# PWR_Buck_2V_4V_4A.net
KiCad netlist of a schematic drawn in Altium Designer
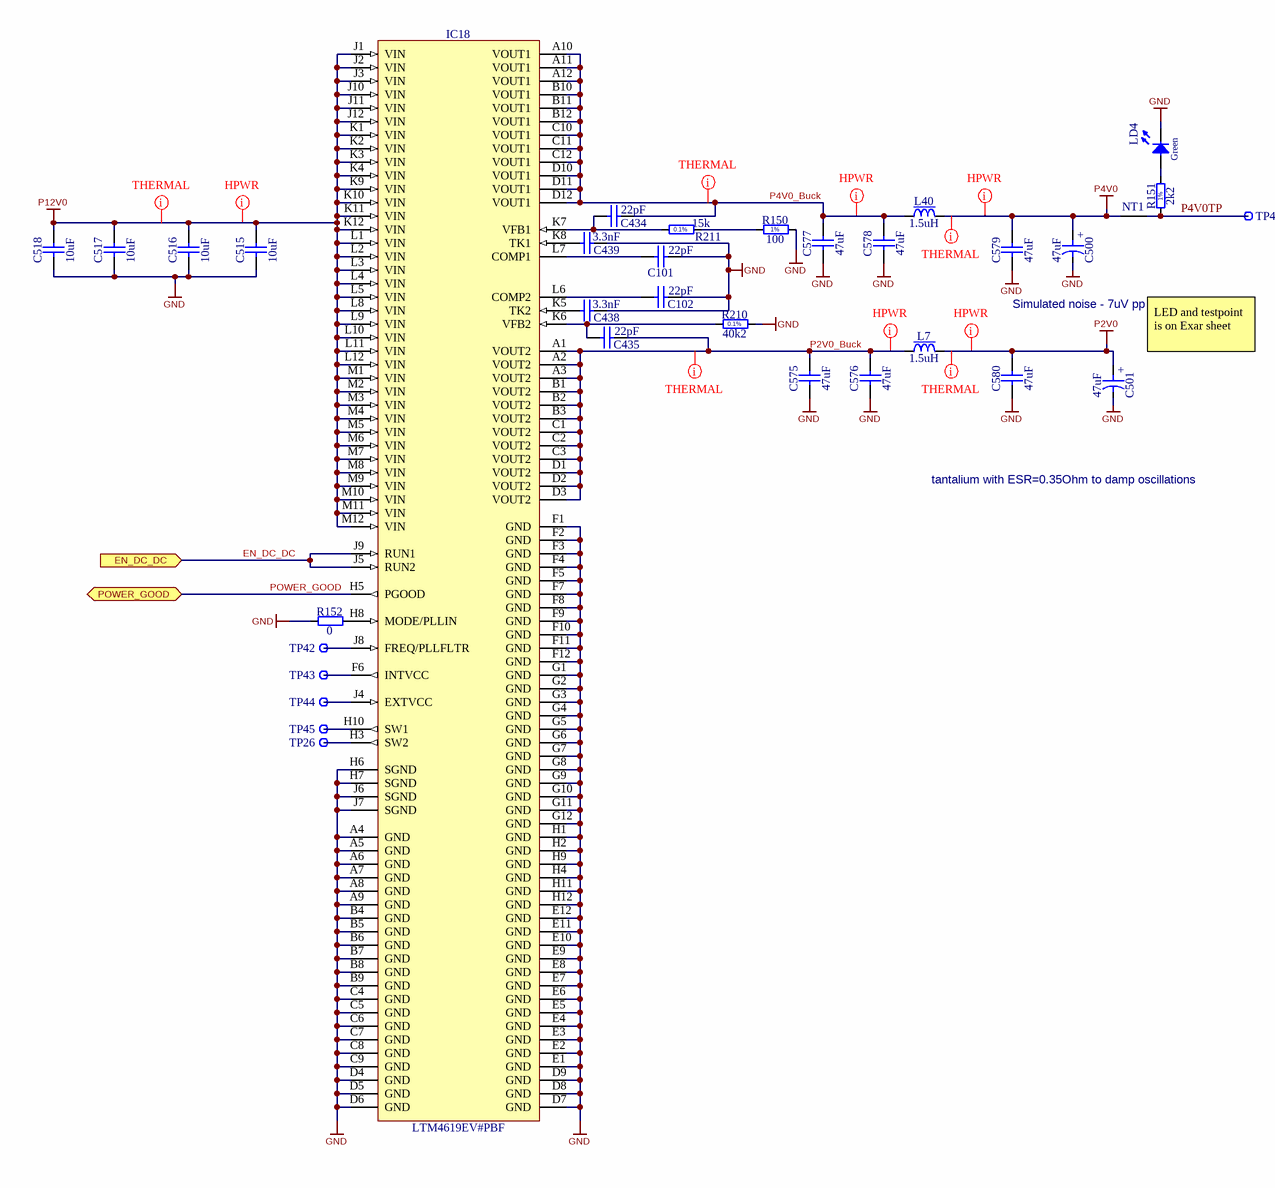
[diagram p0: PWR_Buck_2V_4V_4A.SchDoc]

(export (version "E")
  (design (tool "Eeschema 10.0.6"))
  (components
    (comp (ref "C101")
      (value "22pF")
      (footprint "CAPC1005X55N")
      (description "Non-polarised capacitor")
      (fields
        (field (name "MANUFACTURER PART NUMBER") "CC0402_22PF_50V_5%_C0G")
        (field (name "MANUFACTURER") "GENERIC")
        (field (name "AUTHOR") "CERN DEM JLC")
      )
      (libsource (lib "Capacitors") (part "Capacitor - non polarized"))
    )
    (comp (ref "C102")
      (value "22pF")
      (footprint "CAPC1005X55N")
      (description "Non-polarised capacitor")
      (fields
        (field (name "MANUFACTURER PART NUMBER") "CC0402_22PF_50V_5%_C0G")
        (field (name "MANUFACTURER") "GENERIC")
        (field (name "AUTHOR") "CERN DEM JLC")
      )
      (libsource (lib "Capacitors") (part "Capacitor - non polarized"))
    )
    (comp (ref "C434")
      (value "22pF")
      (footprint "CAPC1005X55N")
      (description "Non-polarised capacitor")
      (fields
        (field (name "MANUFACTURER PART NUMBER") "CC0402_22PF_50V_5%_C0G")
        (field (name "MANUFACTURER") "GENERIC")
        (field (name "AUTHOR") "CERN DEM JLC")
      )
      (libsource (lib "Capacitors") (part "Capacitor - non polarized"))
    )
    (comp (ref "C435")
      (value "22pF")
      (footprint "CAPC1005X55N")
      (description "Non-polarised capacitor")
      (fields
        (field (name "MANUFACTURER PART NUMBER") "CC0402_22PF_50V_5%_C0G")
        (field (name "MANUFACTURER") "GENERIC")
        (field (name "AUTHOR") "CERN DEM JLC")
      )
      (libsource (lib "Capacitors") (part "Capacitor - non polarized"))
    )
    (comp (ref "C438")
      (value "3.3nF")
      (footprint "CAPC1005X55N")
      (description "Non-polarised capacitor")
      (fields
        (field (name "MANUFACTURER PART NUMBER") "CC0402_3.3NF_50V_10%_X7R")
        (field (name "MANUFACTURER") "GENERIC")
        (field (name "AUTHOR") "CERN DEM JLC")
      )
      (libsource (lib "Capacitors") (part "Capacitor - non polarized"))
    )
    (comp (ref "C439")
      (value "3.3nF")
      (footprint "CAPC1005X55N")
      (description "Non-polarised capacitor")
      (fields
        (field (name "MANUFACTURER PART NUMBER") "CC0402_3.3NF_50V_10%_X7R")
        (field (name "MANUFACTURER") "GENERIC")
        (field (name "AUTHOR") "CERN DEM JLC")
      )
      (libsource (lib "Capacitors") (part "Capacitor - non polarized"))
    )
    (comp (ref "C500")
      (value "47uF")
      (footprint "CAPMP6032X280N")
      (description "Polarised capacitor")
      (fields
        (field (name "MANUFACTURER PART NUMBER") "CTE6032-28_47UF_16V_10%_LESR0350")
        (field (name "MANUFACTURER") "GENERIC")
        (field (name "AUTHOR") "CERN DEM JLC")
      )
      (libsource (lib "Capacitors") (part "Capacitor - polarized"))
    )
    (comp (ref "C501")
      (value "47uF")
      (footprint "CAPMP6032X280N")
      (description "Polarised capacitor")
      (fields
        (field (name "MANUFACTURER PART NUMBER") "CTE6032-28_47UF_16V_10%_LESR0350")
        (field (name "MANUFACTURER") "GENERIC")
        (field (name "AUTHOR") "CERN DEM JLC")
      )
      (libsource (lib "Capacitors") (part "Capacitor - polarized"))
    )
    (comp (ref "C515")
      (value "10uF")
      (footprint "CAPC2012X95N")
      (description "Non-polarised capacitor")
      (fields
        (field (name "MANUFACTURER PART NUMBER") "CC0805_10UF_25V_10%_X5R")
        (field (name "MANUFACTURER") "GENERIC")
        (field (name "AUTHOR") "CERN DEM JLC")
      )
      (libsource (lib "Capacitors") (part "Capacitor - non polarized"))
    )
    (comp (ref "C516")
      (value "10uF")
      (footprint "CAPC2012X95N")
      (description "Non-polarised capacitor")
      (fields
        (field (name "MANUFACTURER PART NUMBER") "CC0805_10UF_25V_10%_X5R")
        (field (name "MANUFACTURER") "GENERIC")
        (field (name "AUTHOR") "CERN DEM JLC")
      )
      (libsource (lib "Capacitors") (part "Capacitor - non polarized"))
    )
    (comp (ref "C517")
      (value "10uF")
      (footprint "CAPC2012X95N")
      (description "Non-polarised capacitor")
      (fields
        (field (name "MANUFACTURER PART NUMBER") "CC0805_10UF_25V_10%_X5R")
        (field (name "MANUFACTURER") "GENERIC")
        (field (name "AUTHOR") "CERN DEM JLC")
      )
      (libsource (lib "Capacitors") (part "Capacitor - non polarized"))
    )
    (comp (ref "C518")
      (value "10uF")
      (footprint "CAPC2012X95N")
      (description "Non-polarised capacitor")
      (fields
        (field (name "MANUFACTURER PART NUMBER") "CC0805_10UF_25V_10%_X5R")
        (field (name "MANUFACTURER") "GENERIC")
        (field (name "AUTHOR") "CERN DEM JLC")
      )
      (libsource (lib "Capacitors") (part "Capacitor - non polarized"))
    )
    (comp (ref "C575")
      (value "47uF")
      (footprint "CAPC3225X270N")
      (description "Non-polarised capacitor")
      (fields
        (field (name "MANUFACTURER PART NUMBER") "CC1210_47UF_10V_10%_X7R")
        (field (name "MANUFACTURER") "GENERIC")
        (field (name "AUTHOR") "CERN DEM BC")
      )
      (libsource (lib "Capacitors") (part "Capacitor - non polarized"))
    )
    (comp (ref "C576")
      (value "47uF")
      (footprint "CAPC3225X270N")
      (description "Non-polarised capacitor")
      (fields
        (field (name "MANUFACTURER PART NUMBER") "CC1210_47UF_10V_10%_X7R")
        (field (name "MANUFACTURER") "GENERIC")
        (field (name "AUTHOR") "CERN DEM BC")
      )
      (libsource (lib "Capacitors") (part "Capacitor - non polarized"))
    )
    (comp (ref "C577")
      (value "47uF")
      (footprint "CAPC3225X270N")
      (description "Non-polarised capacitor")
      (fields
        (field (name "MANUFACTURER PART NUMBER") "CC1210_47UF_10V_10%_X7R")
        (field (name "MANUFACTURER") "GENERIC")
        (field (name "AUTHOR") "CERN DEM BC")
      )
      (libsource (lib "Capacitors") (part "Capacitor - non polarized"))
    )
    (comp (ref "C578")
      (value "47uF")
      (footprint "CAPC3225X270N")
      (description "Non-polarised capacitor")
      (fields
        (field (name "MANUFACTURER PART NUMBER") "CC1210_47UF_10V_10%_X7R")
        (field (name "MANUFACTURER") "GENERIC")
        (field (name "AUTHOR") "CERN DEM BC")
      )
      (libsource (lib "Capacitors") (part "Capacitor - non polarized"))
    )
    (comp (ref "C579")
      (value "47uF")
      (footprint "CAPC3225X270N")
      (description "Non-polarised capacitor")
      (fields
        (field (name "MANUFACTURER PART NUMBER") "CC1210_47UF_10V_10%_X7R")
        (field (name "MANUFACTURER") "GENERIC")
        (field (name "AUTHOR") "CERN DEM BC")
      )
      (libsource (lib "Capacitors") (part "Capacitor - non polarized"))
    )
    (comp (ref "C580")
      (value "47uF")
      (footprint "CAPC3225X270N")
      (description "Non-polarised capacitor")
      (fields
        (field (name "MANUFACTURER PART NUMBER") "CC1210_47UF_10V_10%_X7R")
        (field (name "MANUFACTURER") "GENERIC")
        (field (name "AUTHOR") "CERN DEM BC")
      )
      (libsource (lib "Capacitors") (part "Capacitor - non polarized"))
    )
    (comp (ref "IC18")
      (value "LTM4619EV#PBF")
      (footprint "LGA144S127P12X12_1500X1500X292R")
      (description "4.5V-26.5V To 0.8V-5V, Iout 4A Dual DC/DC uModule Regulator")
      (fields (field (name "MANUFACTURER") "LINEAR TECHNOLOGY") (field (name "AUTHOR") "CERN DEM JLC"))
      (libsource (lib "ICs And Semiconductors") (part "LTM4619"))
    )
    (comp (ref "L7")
      (value "1.5uH")
      (footprint "IND_TDK_SPM6530")
      (description "Inductor With Core")
      (fields
        (field (name "MANUFACTURER PART NUMBER") "SPM6530T-1R5M100")
        (field (name "MANUFACTURER") "TDK")
        (field (name "AUTHOR") "CERN DEM MR")
      )
      (libsource (lib "Inductors & Transformers") (part "Inductor With Magnetic core"))
    )
    (comp (ref "L40")
      (value "1.5uH")
      (footprint "IND_TDK_SPM6530")
      (description "Inductor With Core")
      (fields
        (field (name "MANUFACTURER PART NUMBER") "SPM6530T-1R5M100")
        (field (name "MANUFACTURER") "TDK")
        (field (name "AUTHOR") "CERN DEM MR")
      )
      (libsource (lib "Inductors & Transformers") (part "Inductor With Magnetic core"))
    )
    (comp (ref "LD4")
      (value "Green")
      (footprint "LED_KINGBRIGHT_KPH-1608CGCK")
      (description "LED Green 1C 2A")
      (fields
        (field (name "MANUFACTURER PART NUMBER") "KPH-1608CGCK")
        (field (name "MANUFACTURER") "KINGBRIGHT")
        (field (name "AUTHOR") "CERN DEM JLC")
      )
      (libsource (lib "ICs And Semiconductors") (part "LED Green 1C 2A"))
    )
    (comp (ref "NT1")
      (value "Net Tie")
      (footprint "Net Tie")
      (fields (field (name "AUTHOR") "CERN DEM JLC"))
      (libsource (lib "Eletro-mechanical") (part "Net Tie"))
    )
    (comp (ref "R150")
      (value "100")
      (footprint "RESC1005X40N")
      (description "Resistor - 1%")
      (fields
        (field (name "MANUFACTURER PART NUMBER") "R0402_100R_1%_0.0625W_100PPM")
        (field (name "MANUFACTURER") "GENERIC")
        (field (name "AUTHOR") "CERN DEM JLC")
      )
      (libsource (lib "Resistors") (part "Resistor - 1%"))
    )
    (comp (ref "R151")
      (value "2k2")
      (footprint "RESC1005X40N")
      (description "Resistor - 1%")
      (fields
        (field (name "MANUFACTURER PART NUMBER") "R0402_2K2_1%_0.0625W_100PPM")
        (field (name "MANUFACTURER") "GENERIC")
        (field (name "AUTHOR") "CERN DEM JLC")
      )
      (libsource (lib "Resistors") (part "Resistor - 1%"))
    )
    (comp (ref "R152")
      (value "0")
      (footprint "RESC1005X40N")
      (description "Resistor")
      (fields
        (field (name "MANUFACTURER PART NUMBER") "R0402_0R_JUMPER")
        (field (name "MANUFACTURER") "GENERIC")
        (field (name "AUTHOR") "CERN DEM JLC")
      )
      (libsource (lib "Resistors") (part "Resistor"))
    )
    (comp (ref "R210")
      (value "40k2")
      (footprint "RESC1608X55N")
      (description "Resistor - 0.1%")
      (fields
        (field (name "MANUFACTURER PART NUMBER") "R0603_40K2_0.1%_0.063W_10PPM")
        (field (name "MANUFACTURER") "GENERIC")
        (field (name "AUTHOR") "CERN DEM JLC")
      )
      (libsource (lib "Resistors") (part "Resistor - 0.1%"))
    )
    (comp (ref "R211")
      (value "15k")
      (footprint "RESC1608X55N")
      (description "Resistor - 0.1%")
      (fields
        (field (name "MANUFACTURER PART NUMBER") "R0603_15K_0.1%_0.063W_10PPM")
        (field (name "MANUFACTURER") "GENERIC")
        (field (name "AUTHOR") "CERN DEM JLC")
      )
      (libsource (lib "Resistors") (part "Resistor - 0.1%"))
    )
    (comp (ref "TP26")
      (value "Test Point")
      (footprint "TPS127")
      (fields (field (name "PART NUMBER") "SMD_PAD_1.27X1.27MM") (field (name "AUTHOR") "CERN DEM JLC"))
      (libsource (lib "Eletro-mechanical") (part "Test Point"))
    )
    (comp (ref "TP41")
      (value "Test Point")
      (footprint "TPS127")
      (fields (field (name "PART NUMBER") "SMD_PAD_1.27X1.27MM") (field (name "AUTHOR") "CERN DEM JLC"))
      (libsource (lib "Eletro-mechanical") (part "Test Point"))
    )
    (comp (ref "TP42")
      (value "Test Point")
      (footprint "TPS127")
      (fields (field (name "PART NUMBER") "SMD_PAD_1.27X1.27MM") (field (name "AUTHOR") "CERN DEM JLC"))
      (libsource (lib "Eletro-mechanical") (part "Test Point"))
    )
    (comp (ref "TP43")
      (value "Test Point")
      (footprint "TPS127")
      (fields (field (name "PART NUMBER") "SMD_PAD_1.27X1.27MM") (field (name "AUTHOR") "CERN DEM JLC"))
      (libsource (lib "Eletro-mechanical") (part "Test Point"))
    )
    (comp (ref "TP44")
      (value "Test Point")
      (footprint "TPS127")
      (fields (field (name "PART NUMBER") "SMD_PAD_1.27X1.27MM") (field (name "AUTHOR") "CERN DEM JLC"))
      (libsource (lib "Eletro-mechanical") (part "Test Point"))
    )
    (comp (ref "TP45")
      (value "Test Point")
      (footprint "TPS127")
      (fields (field (name "PART NUMBER") "SMD_PAD_1.27X1.27MM") (field (name "AUTHOR") "CERN DEM JLC"))
      (libsource (lib "Eletro-mechanical") (part "Test Point"))
    )
  )
  (nets
    (net (code "1") (name "/EN_DC_DC") (class "Default")
      (node (ref "IC18") (pin "J5") (pinfunction "RUN2_J5") (pintype "input"))
      (node (ref "IC18") (pin "J9") (pinfunction "RUN1_J9") (pintype "input"))
    )
    (net (code "2") (name "/P2V0_Buck") (class "Default")
      (node (ref "C435") (pin "1") (pinfunction "1_1") (pintype "passive"))
      (node (ref "C575") (pin "2") (pinfunction "2_2") (pintype "passive"))
      (node (ref "C576") (pin "2") (pinfunction "2_2") (pintype "passive"))
      (node (ref "IC18") (pin "A1") (pinfunction "VOUT2_A1") (pintype "power_in"))
      (node (ref "IC18") (pin "A2") (pinfunction "VOUT2_A2") (pintype "power_in"))
      (node (ref "IC18") (pin "A3") (pinfunction "VOUT2_A3") (pintype "power_in"))
      (node (ref "IC18") (pin "B1") (pinfunction "VOUT2_B1") (pintype "power_in"))
      (node (ref "IC18") (pin "B2") (pinfunction "VOUT2_B2") (pintype "power_in"))
      (node (ref "IC18") (pin "B3") (pinfunction "VOUT2_B3") (pintype "power_in"))
      (node (ref "IC18") (pin "C1") (pinfunction "VOUT2_C1") (pintype "power_in"))
      (node (ref "IC18") (pin "C2") (pinfunction "VOUT2_C2") (pintype "power_in"))
      (node (ref "IC18") (pin "C3") (pinfunction "VOUT2_C3") (pintype "power_in"))
      (node (ref "IC18") (pin "D1") (pinfunction "VOUT2_D1") (pintype "power_in"))
      (node (ref "IC18") (pin "D2") (pinfunction "VOUT2_D2") (pintype "power_in"))
      (node (ref "IC18") (pin "D3") (pinfunction "VOUT2_D3") (pintype "power_in"))
      (node (ref "L7") (pin "1") (pinfunction "1_1") (pintype "passive"))
    )
    (net (code "3") (name "/P4V0TP") (class "Default")
      (node (ref "NT1") (pin "2") (pinfunction "2_2") (pintype "bidirectional"))
      (node (ref "R151") (pin "1") (pinfunction "1_1") (pintype "passive"))
      (node (ref "TP41") (pin "1") (pinfunction "1_1") (pintype "bidirectional"))
    )
    (net (code "4") (name "/P4V0_Buck") (class "Default")
      (node (ref "C434") (pin "1") (pinfunction "1_1") (pintype "passive"))
      (node (ref "C577") (pin "2") (pinfunction "2_2") (pintype "passive"))
      (node (ref "C578") (pin "2") (pinfunction "2_2") (pintype "passive"))
      (node (ref "IC18") (pin "A10") (pinfunction "VOUT1_A10") (pintype "power_in"))
      (node (ref "IC18") (pin "A11") (pinfunction "VOUT1_A11") (pintype "power_in"))
      (node (ref "IC18") (pin "A12") (pinfunction "VOUT1_A12") (pintype "power_in"))
      (node (ref "IC18") (pin "B10") (pinfunction "VOUT1_B10") (pintype "power_in"))
      (node (ref "IC18") (pin "B11") (pinfunction "VOUT1_B11") (pintype "power_in"))
      (node (ref "IC18") (pin "B12") (pinfunction "VOUT1_B12") (pintype "power_in"))
      (node (ref "IC18") (pin "C10") (pinfunction "VOUT1_C10") (pintype "power_in"))
      (node (ref "IC18") (pin "C11") (pinfunction "VOUT1_C11") (pintype "power_in"))
      (node (ref "IC18") (pin "C12") (pinfunction "VOUT1_C12") (pintype "power_in"))
      (node (ref "IC18") (pin "D10") (pinfunction "VOUT1_D10") (pintype "power_in"))
      (node (ref "IC18") (pin "D11") (pinfunction "VOUT1_D11") (pintype "power_in"))
      (node (ref "IC18") (pin "D12") (pinfunction "VOUT1_D12") (pintype "power_in"))
      (node (ref "L40") (pin "1") (pinfunction "1_1") (pintype "passive"))
    )
    (net (code "5") (name "/POWER_GOOD") (class "Default")
      (node (ref "IC18") (pin "H5") (pinfunction "PGOOD_H5") (pintype "output"))
    )
    (net (code "6") (name "GND") (class "Default")
      (node (ref "C101") (pin "1") (pinfunction "1_1") (pintype "passive"))
      (node (ref "C102") (pin "1") (pinfunction "1_1") (pintype "passive"))
      (node (ref "C438") (pin "2") (pinfunction "2_2") (pintype "passive"))
      (node (ref "C439") (pin "2") (pinfunction "2_2") (pintype "passive"))
      (node (ref "C500") (pin "2") (pinfunction "2_2") (pintype "passive"))
      (node (ref "C501") (pin "2") (pinfunction "2_2") (pintype "passive"))
      (node (ref "C515") (pin "1") (pinfunction "1_1") (pintype "passive"))
      (node (ref "C516") (pin "1") (pinfunction "1_1") (pintype "passive"))
      (node (ref "C517") (pin "1") (pinfunction "1_1") (pintype "passive"))
      (node (ref "C518") (pin "1") (pinfunction "1_1") (pintype "passive"))
      (node (ref "C575") (pin "1") (pinfunction "1_1") (pintype "passive"))
      (node (ref "C576") (pin "1") (pinfunction "1_1") (pintype "passive"))
      (node (ref "C577") (pin "1") (pinfunction "1_1") (pintype "passive"))
      (node (ref "C578") (pin "1") (pinfunction "1_1") (pintype "passive"))
      (node (ref "C579") (pin "1") (pinfunction "1_1") (pintype "passive"))
      (node (ref "C580") (pin "1") (pinfunction "1_1") (pintype "passive"))
      (node (ref "IC18") (pin "A4") (pinfunction "GND_A4") (pintype "power_in"))
      (node (ref "IC18") (pin "A5") (pinfunction "GND_A5") (pintype "power_in"))
      (node (ref "IC18") (pin "A6") (pinfunction "GND_A6") (pintype "power_in"))
      (node (ref "IC18") (pin "A7") (pinfunction "GND_A7") (pintype "power_in"))
      (node (ref "IC18") (pin "A8") (pinfunction "GND_A8") (pintype "power_in"))
      (node (ref "IC18") (pin "A9") (pinfunction "GND_A9") (pintype "power_in"))
      (node (ref "IC18") (pin "B4") (pinfunction "GND_B4") (pintype "power_in"))
      (node (ref "IC18") (pin "B5") (pinfunction "GND_B5") (pintype "power_in"))
      (node (ref "IC18") (pin "B6") (pinfunction "GND_B6") (pintype "power_in"))
      (node (ref "IC18") (pin "B7") (pinfunction "GND_B7") (pintype "power_in"))
      (node (ref "IC18") (pin "B8") (pinfunction "GND_B8") (pintype "power_in"))
      (node (ref "IC18") (pin "B9") (pinfunction "GND_B9") (pintype "power_in"))
      (node (ref "IC18") (pin "C4") (pinfunction "GND_C4") (pintype "power_in"))
      (node (ref "IC18") (pin "C5") (pinfunction "GND_C5") (pintype "power_in"))
      (node (ref "IC18") (pin "C6") (pinfunction "GND_C6") (pintype "power_in"))
      (node (ref "IC18") (pin "C7") (pinfunction "GND_C7") (pintype "power_in"))
      (node (ref "IC18") (pin "C8") (pinfunction "GND_C8") (pintype "power_in"))
      (node (ref "IC18") (pin "C9") (pinfunction "GND_C9") (pintype "power_in"))
      (node (ref "IC18") (pin "D4") (pinfunction "GND_D4") (pintype "power_in"))
      (node (ref "IC18") (pin "D5") (pinfunction "GND_D5") (pintype "power_in"))
      (node (ref "IC18") (pin "D6") (pinfunction "GND_D6") (pintype "power_in"))
      (node (ref "IC18") (pin "D7") (pinfunction "GND_D7") (pintype "power_in"))
      (node (ref "IC18") (pin "D8") (pinfunction "GND_D8") (pintype "power_in"))
      (node (ref "IC18") (pin "D9") (pinfunction "GND_D9") (pintype "power_in"))
      (node (ref "IC18") (pin "E1") (pinfunction "GND_E1") (pintype "power_in"))
      (node (ref "IC18") (pin "E10") (pinfunction "GND_E10") (pintype "power_in"))
      (node (ref "IC18") (pin "E11") (pinfunction "GND_E11") (pintype "power_in"))
      (node (ref "IC18") (pin "E12") (pinfunction "GND_E12") (pintype "power_in"))
      (node (ref "IC18") (pin "E2") (pinfunction "GND_E2") (pintype "power_in"))
      (node (ref "IC18") (pin "E3") (pinfunction "GND_E3") (pintype "power_in"))
      (node (ref "IC18") (pin "E4") (pinfunction "GND_E4") (pintype "power_in"))
      (node (ref "IC18") (pin "E5") (pinfunction "GND_E5") (pintype "power_in"))
      (node (ref "IC18") (pin "E6") (pinfunction "GND_E6") (pintype "power_in"))
      (node (ref "IC18") (pin "E7") (pinfunction "GND_E7") (pintype "power_in"))
      (node (ref "IC18") (pin "E8") (pinfunction "GND_E8") (pintype "power_in"))
      (node (ref "IC18") (pin "E9") (pinfunction "GND_E9") (pintype "power_in"))
      (node (ref "IC18") (pin "F1") (pinfunction "GND_F1") (pintype "power_in"))
      (node (ref "IC18") (pin "F10") (pinfunction "GND_F10") (pintype "power_in"))
      (node (ref "IC18") (pin "F11") (pinfunction "GND_F11") (pintype "power_in"))
      (node (ref "IC18") (pin "F12") (pinfunction "GND_F12") (pintype "power_in"))
      (node (ref "IC18") (pin "F2") (pinfunction "GND_F2") (pintype "power_in"))
      (node (ref "IC18") (pin "F3") (pinfunction "GND_F3") (pintype "power_in"))
      (node (ref "IC18") (pin "F4") (pinfunction "GND_F4") (pintype "power_in"))
      (node (ref "IC18") (pin "F5") (pinfunction "GND_F5") (pintype "power_in"))
      (node (ref "IC18") (pin "F7") (pinfunction "GND_F7") (pintype "power_in"))
      (node (ref "IC18") (pin "F8") (pinfunction "GND_F8") (pintype "power_in"))
      (node (ref "IC18") (pin "F9") (pinfunction "GND_F9") (pintype "power_in"))
      (node (ref "IC18") (pin "G1") (pinfunction "GND_G1") (pintype "power_in"))
      (node (ref "IC18") (pin "G10") (pinfunction "GND_G10") (pintype "power_in"))
      (node (ref "IC18") (pin "G11") (pinfunction "GND_G11") (pintype "power_in"))
      (node (ref "IC18") (pin "G12") (pinfunction "GND_G12") (pintype "power_in"))
      (node (ref "IC18") (pin "G2") (pinfunction "GND_G2") (pintype "power_in"))
      (node (ref "IC18") (pin "G3") (pinfunction "GND_G3") (pintype "power_in"))
      (node (ref "IC18") (pin "G4") (pinfunction "GND_G4") (pintype "power_in"))
      (node (ref "IC18") (pin "G5") (pinfunction "GND_G5") (pintype "power_in"))
      (node (ref "IC18") (pin "G6") (pinfunction "GND_G6") (pintype "power_in"))
      (node (ref "IC18") (pin "G7") (pinfunction "GND_G7") (pintype "power_in"))
      (node (ref "IC18") (pin "G8") (pinfunction "GND_G8") (pintype "power_in"))
      (node (ref "IC18") (pin "G9") (pinfunction "GND_G9") (pintype "power_in"))
      (node (ref "IC18") (pin "H1") (pinfunction "GND_H1") (pintype "power_in"))
      (node (ref "IC18") (pin "H11") (pinfunction "GND_H11") (pintype "power_in"))
      (node (ref "IC18") (pin "H12") (pinfunction "GND_H12") (pintype "power_in"))
      (node (ref "IC18") (pin "H2") (pinfunction "GND_H2") (pintype "power_in"))
      (node (ref "IC18") (pin "H4") (pinfunction "GND_H4") (pintype "power_in"))
      (node (ref "IC18") (pin "H6") (pinfunction "SGND_H6") (pintype "power_in"))
      (node (ref "IC18") (pin "H7") (pinfunction "SGND_H7") (pintype "power_in"))
      (node (ref "IC18") (pin "H9") (pinfunction "GND_H9") (pintype "power_in"))
      (node (ref "IC18") (pin "J6") (pinfunction "SGND_J6") (pintype "power_in"))
      (node (ref "IC18") (pin "J7") (pinfunction "SGND_J7") (pintype "power_in"))
      (node (ref "LD4") (pin "1") (pinfunction "C_1") (pintype "passive"))
      (node (ref "R150") (pin "2") (pinfunction "2_2") (pintype "passive"))
      (node (ref "R152") (pin "1") (pinfunction "1_1") (pintype "passive"))
      (node (ref "R210") (pin "2") (pinfunction "2_2") (pintype "passive"))
    )
    (net (code "7") (name "Net-(IC18-COMP1)") (class "Default")
      (node (ref "C101") (pin "2") (pinfunction "2_2") (pintype "passive"))
      (node (ref "IC18") (pin "L7") (pinfunction "COMP1_L7") (pintype "passive"))
    )
    (net (code "8") (name "Net-(IC18-COMP2)") (class "Default")
      (node (ref "C102") (pin "2") (pinfunction "2_2") (pintype "passive"))
      (node (ref "IC18") (pin "L6") (pinfunction "COMP2_L6") (pintype "passive"))
    )
    (net (code "9") (name "Net-(IC18-EXTVCC)") (class "Default")
      (node (ref "IC18") (pin "J4") (pinfunction "EXTVCC_J4") (pintype "input"))
      (node (ref "TP44") (pin "1") (pinfunction "1_1") (pintype "bidirectional"))
    )
    (net (code "10") (name "Net-(IC18-FREQ{slash}PLLFLTR)") (class "Default")
      (node (ref "IC18") (pin "J8") (pinfunction "FREQ/PLLFLTR_J8") (pintype "input"))
      (node (ref "TP42") (pin "1") (pinfunction "1_1") (pintype "bidirectional"))
    )
    (net (code "11") (name "Net-(IC18-INTVCC)") (class "Default")
      (node (ref "IC18") (pin "F6") (pinfunction "INTVCC_F6") (pintype "output"))
      (node (ref "TP43") (pin "1") (pinfunction "1_1") (pintype "bidirectional"))
    )
    (net (code "12") (name "Net-(IC18-MODE{slash}PLLIN)") (class "Default")
      (node (ref "IC18") (pin "H8") (pinfunction "MODE/PLLIN_H8") (pintype "input"))
      (node (ref "R152") (pin "2") (pinfunction "2_2") (pintype "passive"))
    )
    (net (code "13") (name "Net-(IC18-SW1)") (class "Default")
      (node (ref "IC18") (pin "H10") (pinfunction "SW1_H10") (pintype "output"))
      (node (ref "TP45") (pin "1") (pinfunction "1_1") (pintype "bidirectional"))
    )
    (net (code "14") (name "Net-(IC18-SW2)") (class "Default")
      (node (ref "IC18") (pin "H3") (pinfunction "SW2_H3") (pintype "output"))
      (node (ref "TP26") (pin "1") (pinfunction "1_1") (pintype "bidirectional"))
    )
    (net (code "15") (name "Net-(IC18-TK1)") (class "Default")
      (node (ref "C439") (pin "1") (pinfunction "1_1") (pintype "passive"))
      (node (ref "IC18") (pin "K8") (pinfunction "TK1_K8") (pintype "input"))
    )
    (net (code "16") (name "Net-(IC18-TK2)") (class "Default")
      (node (ref "C438") (pin "1") (pinfunction "1_1") (pintype "passive"))
      (node (ref "IC18") (pin "K5") (pinfunction "TK2_K5") (pintype "input"))
    )
    (net (code "17") (name "Net-(IC18-VFB1)") (class "Default")
      (node (ref "C434") (pin "2") (pinfunction "2_2") (pintype "passive"))
      (node (ref "IC18") (pin "K7") (pinfunction "VFB1_K7") (pintype "input"))
      (node (ref "R211") (pin "1") (pinfunction "1_1") (pintype "passive"))
    )
    (net (code "18") (name "Net-(IC18-VFB2)") (class "Default")
      (node (ref "C435") (pin "2") (pinfunction "2_2") (pintype "passive"))
      (node (ref "IC18") (pin "K6") (pinfunction "VFB2_K6") (pintype "input"))
      (node (ref "R210") (pin "1") (pinfunction "1_1") (pintype "passive"))
    )
    (net (code "19") (name "Net-(LD4-A)") (class "Default")
      (node (ref "LD4") (pin "2") (pinfunction "A_2") (pintype "passive"))
      (node (ref "R151") (pin "2") (pinfunction "2_2") (pintype "passive"))
    )
    (net (code "20") (name "Net-(R150-Pad1)") (class "Default")
      (node (ref "R150") (pin "1") (pinfunction "1_1") (pintype "passive"))
      (node (ref "R211") (pin "2") (pinfunction "2_2") (pintype "passive"))
    )
    (net (code "21") (name "P2V0") (class "Default")
      (node (ref "C501") (pin "1") (pinfunction "1_1") (pintype "passive"))
      (node (ref "C580") (pin "2") (pinfunction "2_2") (pintype "passive"))
      (node (ref "L7") (pin "2") (pinfunction "2_2") (pintype "passive"))
    )
    (net (code "22") (name "P4V0") (class "Default")
      (node (ref "C500") (pin "1") (pinfunction "1_1") (pintype "passive"))
      (node (ref "C579") (pin "2") (pinfunction "2_2") (pintype "passive"))
      (node (ref "L40") (pin "2") (pinfunction "2_2") (pintype "passive"))
      (node (ref "NT1") (pin "1") (pinfunction "1_1") (pintype "bidirectional"))
    )
    (net (code "23") (name "P12V0") (class "Default")
      (node (ref "C515") (pin "2") (pinfunction "2_2") (pintype "passive"))
      (node (ref "C516") (pin "2") (pinfunction "2_2") (pintype "passive"))
      (node (ref "C517") (pin "2") (pinfunction "2_2") (pintype "passive"))
      (node (ref "C518") (pin "2") (pinfunction "2_2") (pintype "passive"))
      (node (ref "IC18") (pin "J1") (pinfunction "VIN_J1") (pintype "input"))
      (node (ref "IC18") (pin "J10") (pinfunction "VIN_J10") (pintype "input"))
      (node (ref "IC18") (pin "J11") (pinfunction "VIN_J11") (pintype "input"))
      (node (ref "IC18") (pin "J12") (pinfunction "VIN_J12") (pintype "input"))
      (node (ref "IC18") (pin "J2") (pinfunction "VIN_J2") (pintype "input"))
      (node (ref "IC18") (pin "J3") (pinfunction "VIN_J3") (pintype "input"))
      (node (ref "IC18") (pin "K1") (pinfunction "VIN_K1") (pintype "input"))
      (node (ref "IC18") (pin "K10") (pinfunction "VIN_K10") (pintype "input"))
      (node (ref "IC18") (pin "K11") (pinfunction "VIN_K11") (pintype "input"))
      (node (ref "IC18") (pin "K12") (pinfunction "VIN_K12") (pintype "input"))
      (node (ref "IC18") (pin "K2") (pinfunction "VIN_K2") (pintype "input"))
      (node (ref "IC18") (pin "K3") (pinfunction "VIN_K3") (pintype "input"))
      (node (ref "IC18") (pin "K4") (pinfunction "VIN_K4") (pintype "input"))
      (node (ref "IC18") (pin "K9") (pinfunction "VIN_K9") (pintype "input"))
      (node (ref "IC18") (pin "L1") (pinfunction "VIN_L1") (pintype "input"))
      (node (ref "IC18") (pin "L10") (pinfunction "VIN_L10") (pintype "input"))
      (node (ref "IC18") (pin "L11") (pinfunction "VIN_L11") (pintype "input"))
      (node (ref "IC18") (pin "L12") (pinfunction "VIN_L12") (pintype "input"))
      (node (ref "IC18") (pin "L2") (pinfunction "VIN_L2") (pintype "input"))
      (node (ref "IC18") (pin "L3") (pinfunction "VIN_L3") (pintype "input"))
      (node (ref "IC18") (pin "L4") (pinfunction "VIN_L4") (pintype "input"))
      (node (ref "IC18") (pin "L5") (pinfunction "VIN_L5") (pintype "input"))
      (node (ref "IC18") (pin "L8") (pinfunction "VIN_L8") (pintype "input"))
      (node (ref "IC18") (pin "L9") (pinfunction "VIN_L9") (pintype "input"))
      (node (ref "IC18") (pin "M1") (pinfunction "VIN_M1") (pintype "input"))
      (node (ref "IC18") (pin "M10") (pinfunction "VIN_M10") (pintype "input"))
      (node (ref "IC18") (pin "M11") (pinfunction "VIN_M11") (pintype "input"))
      (node (ref "IC18") (pin "M12") (pinfunction "VIN_M12") (pintype "input"))
      (node (ref "IC18") (pin "M2") (pinfunction "VIN_M2") (pintype "input"))
      (node (ref "IC18") (pin "M3") (pinfunction "VIN_M3") (pintype "input"))
      (node (ref "IC18") (pin "M4") (pinfunction "VIN_M4") (pintype "input"))
      (node (ref "IC18") (pin "M5") (pinfunction "VIN_M5") (pintype "input"))
      (node (ref "IC18") (pin "M6") (pinfunction "VIN_M6") (pintype "input"))
      (node (ref "IC18") (pin "M7") (pinfunction "VIN_M7") (pintype "input"))
      (node (ref "IC18") (pin "M8") (pinfunction "VIN_M8") (pintype "input"))
      (node (ref "IC18") (pin "M9") (pinfunction "VIN_M9") (pintype "input"))
    )
  )
)
